# ControllerV3_0_2.net
KiCad netlist of a schematic drawn in Altium Designer
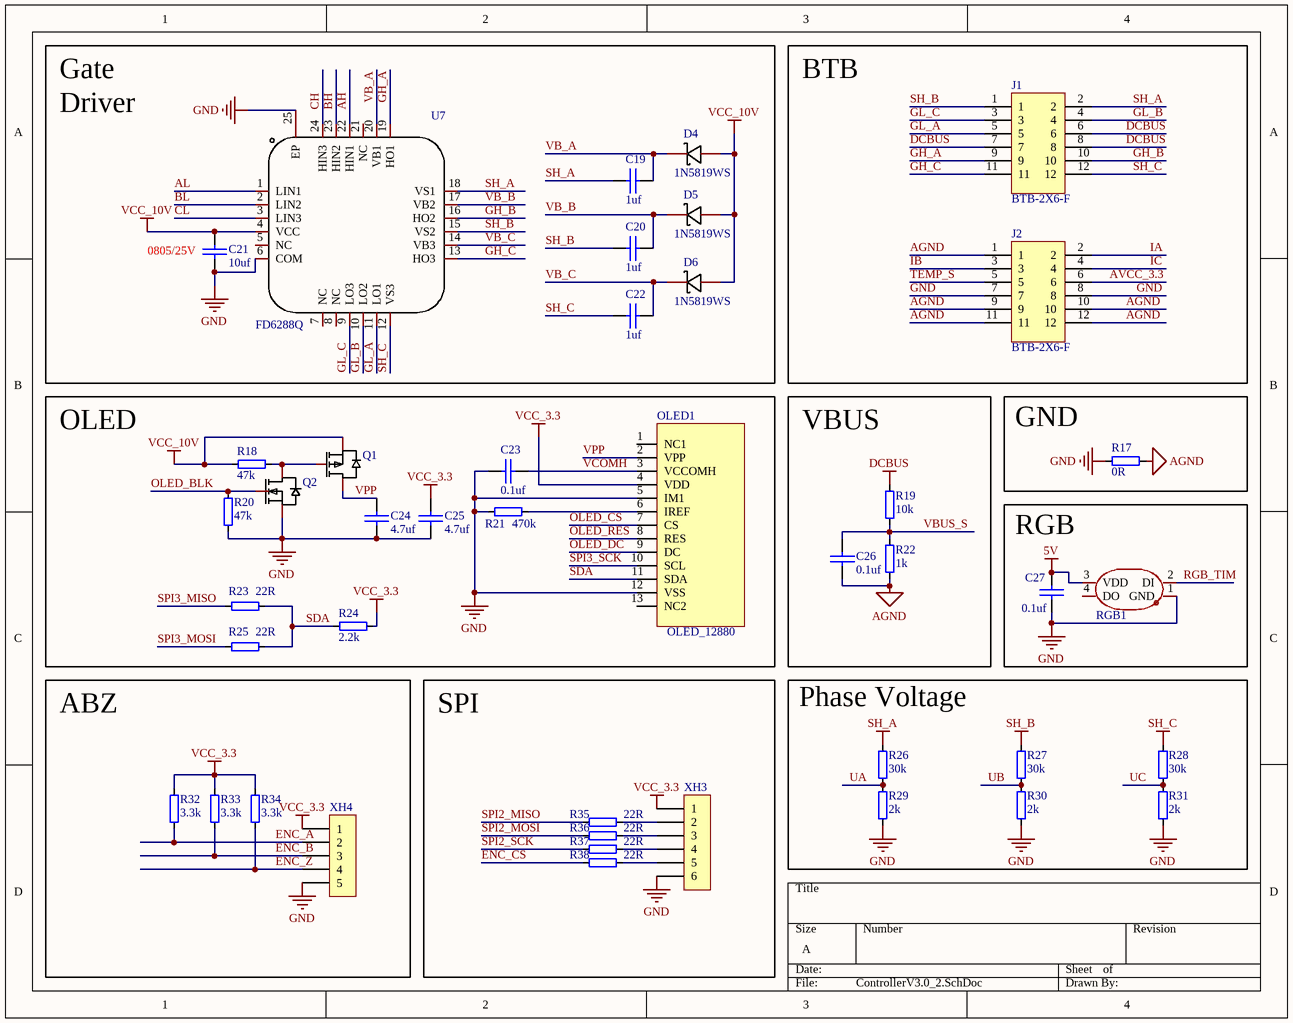
[diagram p0: ControllerV3.0_2.SchDoc]

(export (version "E")
  (design (tool "Eeschema 10.0.6"))
  (components
    (comp (ref "C19")
      (value "1uf")
      (footprint "C0603_S")
      (description "贴片电容")
      (libsource (lib "Controller") (part "CAP"))
    )
    (comp (ref "C20")
      (value "1uf")
      (footprint "C0603_S")
      (description "贴片电容")
      (libsource (lib "Controller") (part "CAP"))
    )
    (comp (ref "C21")
      (value "10uf")
      (footprint "C0805_S")
      (description "贴片电容")
      (libsource (lib "Controller") (part "CAP"))
    )
    (comp (ref "C22")
      (value "1uf")
      (footprint "C0603_S")
      (description "贴片电容")
      (libsource (lib "Controller") (part "CAP"))
    )
    (comp (ref "C23")
      (value "0.1uf")
      (footprint "C0603_S")
      (description "贴片电容")
      (libsource (lib "Controller") (part "CAP"))
    )
    (comp (ref "C24")
      (value "4.7uf")
      (footprint "C0603_S")
      (description "贴片电容")
      (libsource (lib "Controller") (part "CAP"))
    )
    (comp (ref "C25")
      (value "4.7uf")
      (footprint "C0603_S")
      (description "贴片电容")
      (libsource (lib "Controller") (part "CAP"))
    )
    (comp (ref "C26")
      (value "0.1uf")
      (footprint "C0603_S")
      (description "贴片电容")
      (libsource (lib "Controller") (part "CAP"))
    )
    (comp (ref "C27")
      (value "0.1uf")
      (footprint "C0603_S")
      (description "贴片电容")
      (libsource (lib "Controller") (part "CAP"))
    )
    (comp (ref "D4")
      (value "1N5819WS")
      (footprint "SOD-323")
      (description "肖特基二极管")
      (fields (field (name "MANUFACTURER") "Hottech(合科泰)"))
      (libsource (lib "Controller") (part "1N5819WS"))
    )
    (comp (ref "D5")
      (value "1N5819WS")
      (footprint "SOD-323")
      (description "肖特基二极管")
      (fields (field (name "MANUFACTURER") "Hottech(合科泰)"))
      (libsource (lib "Controller") (part "1N5819WS"))
    )
    (comp (ref "D6")
      (value "1N5819WS")
      (footprint "SOD-323")
      (description "肖特基二极管")
      (fields (field (name "MANUFACTURER") "Hottech(合科泰)"))
      (libsource (lib "Controller") (part "1N5819WS"))
    )
    (comp (ref "J1")
      (value "BTB-2X6-F")
      (footprint "BTB-F-0.8mm-2x6P")
      (description "0.8间距2x6P母座")
      (libsource (lib "Controller") (part "BTB-2X6-F"))
    )
    (comp (ref "J2")
      (value "BTB-2X6-F")
      (footprint "BTB-F-0.8mm-2x6P")
      (description "0.8间距2x6P母座")
      (libsource (lib "Controller") (part "BTB-2X6-F"))
    )
    (comp (ref "OLED1")
      (value "OLED_12880")
      (footprint "OLED_12880")
      (description "OLED_128*80")
      (libsource (lib "Controller") (part "OLED_12880"))
    )
    (comp (ref "Q1")
      (value "FDN338P")
      (footprint "SOT-23-3")
      (description "P沟道 耐压:20V 电流:2A")
      (fields (field (name "MANUFACTURER") "TECH PUBLIC(台舟)"))
      (libsource (lib "Controller") (part "FDN338P"))
    )
    (comp (ref "Q2")
      (value "FDN335N")
      (footprint "SOT-23-3")
      (description "N沟道 耐压:20V 电流:1.7A")
      (fields (field (name "MANUFACTURER") "TECH PUBLIC(台舟)"))
      (libsource (lib "Controller") (part "FDN335N"))
    )
    (comp (ref "R17")
      (value "0R")
      (footprint "R0603_S")
      (description "贴片电阻")
      (libsource (lib "Controller") (part "RES"))
    )
    (comp (ref "R18")
      (value "47k")
      (footprint "R0603_S")
      (description "贴片电阻")
      (libsource (lib "Controller") (part "RES"))
    )
    (comp (ref "R19")
      (value "10k")
      (footprint "R0603_S")
      (description "贴片电阻")
      (libsource (lib "Controller") (part "RES"))
    )
    (comp (ref "R20")
      (value "47k")
      (footprint "R0603_S")
      (description "贴片电阻")
      (libsource (lib "Controller") (part "RES"))
    )
    (comp (ref "R21")
      (value "470k")
      (footprint "R0603_S")
      (description "贴片电阻")
      (libsource (lib "Controller") (part "RES"))
    )
    (comp (ref "R22")
      (value "1k")
      (footprint "R0603_S")
      (description "贴片电阻")
      (libsource (lib "Controller") (part "RES"))
    )
    (comp (ref "R23")
      (value "22R")
      (footprint "R0603_S")
      (description "贴片电阻")
      (libsource (lib "Controller") (part "RES"))
    )
    (comp (ref "R24")
      (value "2.2k")
      (footprint "R0603_S")
      (description "贴片电阻")
      (libsource (lib "Controller") (part "RES"))
    )
    (comp (ref "R25")
      (value "22R")
      (footprint "R0603_S")
      (description "贴片电阻")
      (libsource (lib "Controller") (part "RES"))
    )
    (comp (ref "R26")
      (value "30k")
      (footprint "R0603_S")
      (description "贴片电阻")
      (libsource (lib "Controller") (part "RES"))
    )
    (comp (ref "R27")
      (value "30k")
      (footprint "R0603_S")
      (description "贴片电阻")
      (libsource (lib "Controller") (part "RES"))
    )
    (comp (ref "R28")
      (value "30k")
      (footprint "R0603_S")
      (description "贴片电阻")
      (libsource (lib "Controller") (part "RES"))
    )
    (comp (ref "R29")
      (value "2k")
      (footprint "R0603_S")
      (description "贴片电阻")
      (libsource (lib "Controller") (part "RES"))
    )
    (comp (ref "R30")
      (value "2k")
      (footprint "R0603_S")
      (description "贴片电阻")
      (libsource (lib "Controller") (part "RES"))
    )
    (comp (ref "R31")
      (value "2k")
      (footprint "R0603_S")
      (description "贴片电阻")
      (libsource (lib "Controller") (part "RES"))
    )
    (comp (ref "R32")
      (value "3.3k")
      (footprint "R0603_S")
      (description "贴片电阻")
      (libsource (lib "Controller") (part "RES"))
    )
    (comp (ref "R33")
      (value "3.3k")
      (footprint "R0603_S")
      (description "贴片电阻")
      (libsource (lib "Controller") (part "RES"))
    )
    (comp (ref "R34")
      (value "3.3k")
      (footprint "R0603_S")
      (description "贴片电阻")
      (libsource (lib "Controller") (part "RES"))
    )
    (comp (ref "R35")
      (value "22R")
      (footprint "R0603_S")
      (description "贴片电阻")
      (libsource (lib "Controller") (part "RES"))
    )
    (comp (ref "R36")
      (value "22R")
      (footprint "R0603_S")
      (description "贴片电阻")
      (libsource (lib "Controller") (part "RES"))
    )
    (comp (ref "R37")
      (value "22R")
      (footprint "R0603_S")
      (description "贴片电阻")
      (libsource (lib "Controller") (part "RES"))
    )
    (comp (ref "R38")
      (value "22R")
      (footprint "R0603_S")
      (description "贴片电阻")
      (libsource (lib "Controller") (part "RES"))
    )
    (comp (ref "RGB1")
      (value "XL-3528RGBW-WS2812B")
      (footprint "LED-SMD_4P")
      (description "发光颜色:RGB三色")
      (fields (field (name "MANUFACTURER") "XINGLIGHT(成兴光)"))
      (libsource (lib "Controller") (part "XL-3528RGBW-WS2812B"))
    )
    (comp (ref "U7")
      (value "FD6288Q")
      (footprint "QFN-24-EP(4x4)")
      (fields (field (name "MANUFACTURER") "Fortior Tech(峰岹)"))
      (libsource (lib "Controller") (part "FD6288Q"))
    )
    (comp (ref "XH3")
      (value "XH2.54-WS-6P")
      (footprint "XH2.54-WS-6P")
      (libsource (lib "Controller") (part "XH2.54-WS-6P"))
    )
    (comp (ref "XH4")
      (value "XH2.54-WS-5P")
      (footprint "XH2.54-WS-5P")
      (libsource (lib "Controller") (part "XH2.54-WS-5P"))
    )
  )
  (nets
    (net (code "1") (name "/AH") (class "Default")
      (node (ref "U7") (pin "22") (pinfunction "HIN1_22") (pintype "passive"))
    )
    (net (code "2") (name "/AL") (class "Default")
      (node (ref "U7") (pin "1") (pinfunction "LIN1_1") (pintype "passive"))
    )
    (net (code "3") (name "/AVCC_3.3") (class "Default")
      (node (ref "J2") (pin "6") (pinfunction "6_6") (pintype "passive"))
    )
    (net (code "4") (name "/BH") (class "Default")
      (node (ref "U7") (pin "23") (pinfunction "HIN2_23") (pintype "passive"))
    )
    (net (code "5") (name "/BL") (class "Default")
      (node (ref "U7") (pin "2") (pinfunction "LIN2_2") (pintype "passive"))
    )
    (net (code "6") (name "/CH") (class "Default")
      (node (ref "U7") (pin "24") (pinfunction "HIN3_24") (pintype "passive"))
    )
    (net (code "7") (name "/CL") (class "Default")
      (node (ref "U7") (pin "3") (pinfunction "LIN3_3") (pintype "passive"))
    )
    (net (code "8") (name "/ENC_A") (class "Default")
      (node (ref "R32") (pin "1") (pinfunction "1_1") (pintype "passive"))
      (node (ref "XH4") (pin "2") (pinfunction "2_2") (pintype "passive"))
    )
    (net (code "9") (name "/ENC_B") (class "Default")
      (node (ref "R33") (pin "1") (pinfunction "1_1") (pintype "passive"))
      (node (ref "XH4") (pin "3") (pinfunction "3_3") (pintype "passive"))
    )
    (net (code "10") (name "/ENC_CS") (class "Default")
      (node (ref "R38") (pin "1") (pinfunction "1_1") (pintype "passive"))
    )
    (net (code "11") (name "/ENC_Z") (class "Default")
      (node (ref "R34") (pin "1") (pinfunction "1_1") (pintype "passive"))
      (node (ref "XH4") (pin "4") (pinfunction "4_4") (pintype "passive"))
    )
    (net (code "12") (name "/GH_A") (class "Default")
      (node (ref "J1") (pin "9") (pinfunction "9_9") (pintype "passive"))
      (node (ref "U7") (pin "19") (pinfunction "HO1_19") (pintype "passive"))
    )
    (net (code "13") (name "/GH_B") (class "Default")
      (node (ref "J1") (pin "10") (pinfunction "10_10") (pintype "passive"))
      (node (ref "U7") (pin "16") (pinfunction "HO2_16") (pintype "passive"))
    )
    (net (code "14") (name "/GH_C") (class "Default")
      (node (ref "J1") (pin "11") (pinfunction "11_11") (pintype "passive"))
      (node (ref "U7") (pin "13") (pinfunction "HO3_13") (pintype "passive"))
    )
    (net (code "15") (name "/GL_A") (class "Default")
      (node (ref "J1") (pin "5") (pinfunction "5_5") (pintype "passive"))
      (node (ref "U7") (pin "11") (pinfunction "LO1_11") (pintype "passive"))
    )
    (net (code "16") (name "/GL_B") (class "Default")
      (node (ref "J1") (pin "4") (pinfunction "4_4") (pintype "passive"))
      (node (ref "U7") (pin "10") (pinfunction "LO2_10") (pintype "passive"))
    )
    (net (code "17") (name "/GL_C") (class "Default")
      (node (ref "J1") (pin "3") (pinfunction "3_3") (pintype "passive"))
      (node (ref "U7") (pin "9") (pinfunction "LO3_9") (pintype "passive"))
    )
    (net (code "18") (name "/IA") (class "Default")
      (node (ref "J2") (pin "2") (pinfunction "2_2") (pintype "passive"))
    )
    (net (code "19") (name "/IB") (class "Default")
      (node (ref "J2") (pin "3") (pinfunction "3_3") (pintype "passive"))
    )
    (net (code "20") (name "/IC") (class "Default")
      (node (ref "J2") (pin "4") (pinfunction "4_4") (pintype "passive"))
    )
    (net (code "21") (name "/OLED_BLK") (class "Default")
      (node (ref "Q2") (pin "1") (pinfunction "G_1") (pintype "passive"))
      (node (ref "R20") (pin "2") (pinfunction "2_2") (pintype "passive"))
    )
    (net (code "22") (name "/OLED_CS") (class "Default")
      (node (ref "OLED1") (pin "7") (pinfunction "CS_7") (pintype "passive"))
    )
    (net (code "23") (name "/OLED_DC") (class "Default")
      (node (ref "OLED1") (pin "9") (pinfunction "DC_9") (pintype "passive"))
    )
    (net (code "24") (name "/OLED_RES") (class "Default")
      (node (ref "OLED1") (pin "8") (pinfunction "RES_8") (pintype "passive"))
    )
    (net (code "25") (name "/RGB_TIM") (class "Default")
      (node (ref "RGB1") (pin "2") (pinfunction "DI_2") (pintype "passive"))
    )
    (net (code "26") (name "/SDA") (class "Default")
      (node (ref "OLED1") (pin "11") (pinfunction "SDA_11") (pintype "passive"))
      (node (ref "R23") (pin "2") (pinfunction "2_2") (pintype "passive"))
      (node (ref "R24") (pin "2") (pinfunction "2_2") (pintype "passive"))
      (node (ref "R25") (pin "2") (pinfunction "2_2") (pintype "passive"))
    )
    (net (code "27") (name "/SPI2_MISO") (class "Default")
      (node (ref "R35") (pin "1") (pinfunction "1_1") (pintype "passive"))
    )
    (net (code "28") (name "/SPI2_MOSI") (class "Default")
      (node (ref "R36") (pin "1") (pinfunction "1_1") (pintype "passive"))
    )
    (net (code "29") (name "/SPI2_SCK") (class "Default")
      (node (ref "R37") (pin "1") (pinfunction "1_1") (pintype "passive"))
    )
    (net (code "30") (name "/SPI3_MISO") (class "Default")
      (node (ref "R23") (pin "1") (pinfunction "1_1") (pintype "passive"))
    )
    (net (code "31") (name "/SPI3_MOSI") (class "Default")
      (node (ref "R25") (pin "1") (pinfunction "1_1") (pintype "passive"))
    )
    (net (code "32") (name "/SPI3_SCK") (class "Default")
      (node (ref "OLED1") (pin "10") (pinfunction "SCL_10") (pintype "passive"))
    )
    (net (code "33") (name "/TEMP_S") (class "Default")
      (node (ref "J2") (pin "5") (pinfunction "5_5") (pintype "passive"))
    )
    (net (code "34") (name "/UA") (class "Default")
      (node (ref "R26") (pin "1") (pinfunction "1_1") (pintype "passive"))
      (node (ref "R29") (pin "2") (pinfunction "2_2") (pintype "passive"))
    )
    (net (code "35") (name "/UB") (class "Default")
      (node (ref "R27") (pin "1") (pinfunction "1_1") (pintype "passive"))
      (node (ref "R30") (pin "2") (pinfunction "2_2") (pintype "passive"))
    )
    (net (code "36") (name "/UC") (class "Default")
      (node (ref "R28") (pin "1") (pinfunction "1_1") (pintype "passive"))
      (node (ref "R31") (pin "2") (pinfunction "2_2") (pintype "passive"))
    )
    (net (code "37") (name "/VBUS_S") (class "Default")
      (node (ref "C26") (pin "1") (pinfunction "1_1") (pintype "passive"))
      (node (ref "R19") (pin "1") (pinfunction "1_1") (pintype "passive"))
      (node (ref "R22") (pin "2") (pinfunction "2_2") (pintype "passive"))
    )
    (net (code "38") (name "/VB_A") (class "Default")
      (node (ref "C19") (pin "2") (pinfunction "2_2") (pintype "passive"))
      (node (ref "D4") (pin "1") (pinfunction "K_1") (pintype "passive"))
      (node (ref "U7") (pin "20") (pinfunction "VB1_20") (pintype "passive"))
    )
    (net (code "39") (name "/VB_B") (class "Default")
      (node (ref "C20") (pin "2") (pinfunction "2_2") (pintype "passive"))
      (node (ref "D5") (pin "1") (pinfunction "K_1") (pintype "passive"))
      (node (ref "U7") (pin "17") (pinfunction "VB2_17") (pintype "passive"))
    )
    (net (code "40") (name "/VB_C") (class "Default")
      (node (ref "C22") (pin "2") (pinfunction "2_2") (pintype "passive"))
      (node (ref "D6") (pin "1") (pinfunction "K_1") (pintype "passive"))
      (node (ref "U7") (pin "14") (pinfunction "VB3_14") (pintype "passive"))
    )
    (net (code "41") (name "/VCOMH") (class "Default")
      (node (ref "C23") (pin "2") (pinfunction "2_2") (pintype "passive"))
      (node (ref "OLED1") (pin "3") (pinfunction "VCCOMH_3") (pintype "passive"))
    )
    (net (code "42") (name "/VPP") (class "Default")
      (node (ref "C24") (pin "2") (pinfunction "2_2") (pintype "passive"))
      (node (ref "OLED1") (pin "2") (pinfunction "VPP_2") (pintype "passive"))
      (node (ref "Q1") (pin "3") (pinfunction "D_3") (pintype "passive"))
    )
    (net (code "43") (name "5V") (class "Default")
      (node (ref "C27") (pin "1") (pinfunction "1_1") (pintype "passive"))
      (node (ref "RGB1") (pin "3") (pinfunction "VDD_3") (pintype "passive"))
    )
    (net (code "44") (name "AGND") (class "Default")
      (node (ref "C26") (pin "2") (pinfunction "2_2") (pintype "passive"))
      (node (ref "J2") (pin "1") (pinfunction "1_1") (pintype "passive"))
      (node (ref "J2") (pin "10") (pinfunction "10_10") (pintype "passive"))
      (node (ref "J2") (pin "11") (pinfunction "11_11") (pintype "passive"))
      (node (ref "J2") (pin "12") (pinfunction "12_12") (pintype "passive"))
      (node (ref "J2") (pin "9") (pinfunction "9_9") (pintype "passive"))
      (node (ref "R17") (pin "1") (pinfunction "1_1") (pintype "passive"))
      (node (ref "R22") (pin "1") (pinfunction "1_1") (pintype "passive"))
    )
    (net (code "45") (name "DCBUS") (class "Default")
      (node (ref "J1") (pin "6") (pinfunction "6_6") (pintype "passive"))
      (node (ref "J1") (pin "7") (pinfunction "7_7") (pintype "passive"))
      (node (ref "J1") (pin "8") (pinfunction "8_8") (pintype "passive"))
      (node (ref "R19") (pin "2") (pinfunction "2_2") (pintype "passive"))
    )
    (net (code "46") (name "GND") (class "Default")
      (node (ref "C21") (pin "2") (pinfunction "2_2") (pintype "passive"))
      (node (ref "C23") (pin "1") (pinfunction "1_1") (pintype "passive"))
      (node (ref "C24") (pin "1") (pinfunction "1_1") (pintype "passive"))
      (node (ref "C25") (pin "1") (pinfunction "1_1") (pintype "passive"))
      (node (ref "C27") (pin "2") (pinfunction "2_2") (pintype "passive"))
      (node (ref "J2") (pin "7") (pinfunction "7_7") (pintype "passive"))
      (node (ref "J2") (pin "8") (pinfunction "8_8") (pintype "passive"))
      (node (ref "OLED1") (pin "12") (pinfunction "VSS_12") (pintype "passive"))
      (node (ref "OLED1") (pin "5") (pinfunction "IM1_5") (pintype "passive"))
      (node (ref "Q2") (pin "2") (pinfunction "S_2") (pintype "passive"))
      (node (ref "R17") (pin "2") (pinfunction "2_2") (pintype "passive"))
      (node (ref "R20") (pin "1") (pinfunction "1_1") (pintype "passive"))
      (node (ref "R21") (pin "1") (pinfunction "1_1") (pintype "passive"))
      (node (ref "R29") (pin "1") (pinfunction "1_1") (pintype "passive"))
      (node (ref "R30") (pin "1") (pinfunction "1_1") (pintype "passive"))
      (node (ref "R31") (pin "1") (pinfunction "1_1") (pintype "passive"))
      (node (ref "RGB1") (pin "1") (pinfunction "GND_1") (pintype "passive"))
      (node (ref "U7") (pin "25") (pinfunction "EP_25") (pintype "passive"))
      (node (ref "U7") (pin "6") (pinfunction "COM_6") (pintype "passive"))
      (node (ref "XH3") (pin "6") (pinfunction "6_6") (pintype "passive"))
      (node (ref "XH4") (pin "5") (pinfunction "5_5") (pintype "passive"))
    )
    (net (code "47") (name "Net-(OLED1-IREF)") (class "Default")
      (node (ref "OLED1") (pin "6") (pinfunction "IREF_6") (pintype "passive"))
      (node (ref "R21") (pin "2") (pinfunction "2_2") (pintype "passive"))
    )
    (net (code "48") (name "Net-(Q1-G)") (class "Default")
      (node (ref "Q1") (pin "1") (pinfunction "G_1") (pintype "passive"))
      (node (ref "Q2") (pin "3") (pinfunction "D_3") (pintype "passive"))
      (node (ref "R18") (pin "1") (pinfunction "1_1") (pintype "passive"))
    )
    (net (code "49") (name "Net-(R35-Pad2)") (class "Default")
      (node (ref "R35") (pin "2") (pinfunction "2_2") (pintype "passive"))
      (node (ref "XH3") (pin "2") (pinfunction "2_2") (pintype "passive"))
    )
    (net (code "50") (name "Net-(R36-Pad2)") (class "Default")
      (node (ref "R36") (pin "2") (pinfunction "2_2") (pintype "passive"))
      (node (ref "XH3") (pin "3") (pinfunction "3_3") (pintype "passive"))
    )
    (net (code "51") (name "Net-(R37-Pad2)") (class "Default")
      (node (ref "R37") (pin "2") (pinfunction "2_2") (pintype "passive"))
      (node (ref "XH3") (pin "4") (pinfunction "4_4") (pintype "passive"))
    )
    (net (code "52") (name "Net-(R38-Pad2)") (class "Default")
      (node (ref "R38") (pin "2") (pinfunction "2_2") (pintype "passive"))
      (node (ref "XH3") (pin "5") (pinfunction "5_5") (pintype "passive"))
    )
    (net (code "53") (name "SH_A") (class "Default")
      (node (ref "C19") (pin "1") (pinfunction "1_1") (pintype "passive"))
      (node (ref "J1") (pin "2") (pinfunction "2_2") (pintype "passive"))
      (node (ref "R26") (pin "2") (pinfunction "2_2") (pintype "passive"))
      (node (ref "U7") (pin "18") (pinfunction "VS1_18") (pintype "passive"))
    )
    (net (code "54") (name "SH_B") (class "Default")
      (node (ref "C20") (pin "1") (pinfunction "1_1") (pintype "passive"))
      (node (ref "J1") (pin "1") (pinfunction "1_1") (pintype "passive"))
      (node (ref "R27") (pin "2") (pinfunction "2_2") (pintype "passive"))
      (node (ref "U7") (pin "15") (pinfunction "VS2_15") (pintype "passive"))
    )
    (net (code "55") (name "SH_C") (class "Default")
      (node (ref "C22") (pin "1") (pinfunction "1_1") (pintype "passive"))
      (node (ref "J1") (pin "12") (pinfunction "12_12") (pintype "passive"))
      (node (ref "R28") (pin "2") (pinfunction "2_2") (pintype "passive"))
      (node (ref "U7") (pin "12") (pinfunction "VS3_12") (pintype "passive"))
    )
    (net (code "56") (name "VCC_3.3") (class "Default")
      (node (ref "C25") (pin "2") (pinfunction "2_2") (pintype "passive"))
      (node (ref "OLED1") (pin "4") (pinfunction "VDD_4") (pintype "passive"))
      (node (ref "R24") (pin "1") (pinfunction "1_1") (pintype "passive"))
      (node (ref "R32") (pin "2") (pinfunction "2_2") (pintype "passive"))
      (node (ref "R33") (pin "2") (pinfunction "2_2") (pintype "passive"))
      (node (ref "R34") (pin "2") (pinfunction "2_2") (pintype "passive"))
      (node (ref "XH3") (pin "1") (pinfunction "1_1") (pintype "passive"))
      (node (ref "XH4") (pin "1") (pinfunction "1_1") (pintype "passive"))
    )
    (net (code "57") (name "VCC_10V") (class "Default")
      (node (ref "C21") (pin "1") (pinfunction "1_1") (pintype "passive"))
      (node (ref "D4") (pin "2") (pinfunction "A_2") (pintype "passive"))
      (node (ref "D5") (pin "2") (pinfunction "A_2") (pintype "passive"))
      (node (ref "D6") (pin "2") (pinfunction "A_2") (pintype "passive"))
      (node (ref "Q1") (pin "2") (pinfunction "S_2") (pintype "passive"))
      (node (ref "R18") (pin "2") (pinfunction "2_2") (pintype "passive"))
      (node (ref "U7") (pin "4") (pinfunction "VCC_4") (pintype "passive"))
    )
    (net (code "58") (name "unconnected-(OLED1-NC1-Pad1)") (class "Default")
      (node (ref "OLED1") (pin "1") (pinfunction "NC1_1") (pintype "passive"))
    )
    (net (code "59") (name "unconnected-(OLED1-NC2-Pad13)") (class "Default")
      (node (ref "OLED1") (pin "13") (pinfunction "NC2_13") (pintype "passive"))
    )
    (net (code "60") (name "unconnected-(RGB1-DO-Pad4)") (class "Default")
      (node (ref "RGB1") (pin "4") (pinfunction "DO_4") (pintype "passive"))
    )
    (net (code "61") (name "unconnected-(U7-NC-Pad5)") (class "Default")
      (node (ref "U7") (pin "5") (pinfunction "NC_5") (pintype "passive"))
    )
    (net (code "62") (name "unconnected-(U7-NC-Pad7)") (class "Default")
      (node (ref "U7") (pin "7") (pinfunction "NC_7") (pintype "passive"))
    )
    (net (code "63") (name "unconnected-(U7-NC-Pad8)") (class "Default")
      (node (ref "U7") (pin "8") (pinfunction "NC_8") (pintype "passive"))
    )
    (net (code "64") (name "unconnected-(U7-NC-Pad21)") (class "Default")
      (node (ref "U7") (pin "21") (pinfunction "NC_21") (pintype "passive"))
    )
  )
)
